# 2021-04-16_BOSS-RoboClaw-Breakout.net
KiCad netlist of a schematic drawn in EAGLE
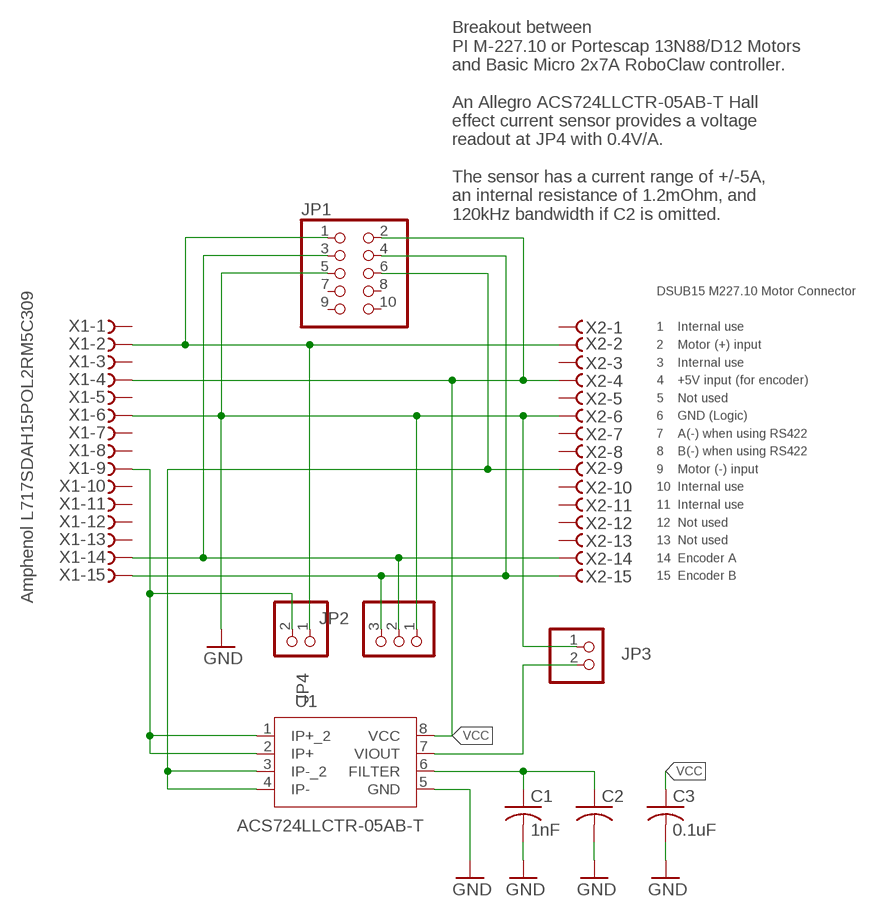
[diagram p0: schematic, sheet 1]

(export (version "E")
  (design (tool "Eeschema 10.0.6"))
  (components
    (comp (ref "C1")
      (value "1nF")
      (footprint "eagle-import:C0805")
      (libsource (lib "eagle-import") (part "C-USC0805"))
    )
    (comp (ref "C2")
      (value "C-USC0805")
      (footprint "eagle-import:C0805")
      (libsource (lib "eagle-import") (part "C-USC0805"))
    )
    (comp (ref "C3")
      (value "0.1uF")
      (footprint "eagle-import:C0805")
      (libsource (lib "eagle-import") (part "C-USC0805"))
    )
    (comp (ref "JP1")
      (value "PINHD-2X5")
      (footprint "eagle-import:2X05")
      (libsource (lib "eagle-import") (part "PINHD-2X5"))
    )
    (comp (ref "JP2")
      (value "PINHD-1X3")
      (footprint "eagle-import:1X03")
      (libsource (lib "eagle-import") (part "PINHD-1X3"))
    )
    (comp (ref "JP3")
      (value "PINHD-1X2")
      (footprint "eagle-import:1X02")
      (libsource (lib "eagle-import") (part "PINHD-1X2"))
    )
    (comp (ref "JP4")
      (value "PINHD-1X2")
      (footprint "eagle-import:1X02")
      (libsource (lib "eagle-import") (part "PINHD-1X2"))
    )
    (comp (ref "U1")
      (value "ACS724LLCTR-05AB-T")
      (footprint "eagle-import:IC8_ACS724LLCTR-05AB-T_ALM")
      (fields (field (name "COPYRIGHT") "Copyright (C) 2018 Accelerated Designs. All rights reserved"))
      (libsource (lib "eagle-import") (part "CURRENTSENSOR-ACS724LLCTR-05AB-T"))
    )
    (comp (ref "X1")
      (value "Amphenol L717SDAH15POL2RM5C309")
      (footprint "eagle-import:H2M15ST")
      (libsource (lib "eagle-import") (part "D-SUB15-H2M15ST"))
    )
    (comp (ref "X2")
      (value "Amphenol L77SDAH15SOL2RM8C309")
      (footprint "eagle-import:H2R15ST")
      (libsource (lib "eagle-import") (part "D-SUB15-H2R15ST"))
    )
  )
  (nets
    (net (code "1") (name "GND") (class "Default")
      (node (ref "C1") (pin "2") (pinfunction "2_2") (pintype "passive"))
      (node (ref "C2") (pin "2") (pinfunction "2_2") (pintype "passive"))
      (node (ref "C3") (pin "2") (pinfunction "2_2") (pintype "passive"))
      (node (ref "JP1") (pin "5") (pinfunction "5_5") (pintype "passive"))
      (node (ref "JP2") (pin "1") (pinfunction "1_1") (pintype "passive"))
      (node (ref "JP3") (pin "1") (pinfunction "1_1") (pintype "passive"))
      (node (ref "U1") (pin "5") (pinfunction "GND_5") (pintype "passive"))
      (node (ref "X1") (pin "6") (pinfunction "F_6") (pintype "passive"))
      (node (ref "X2") (pin "6") (pinfunction "F_6") (pintype "passive"))
    )
    (net (code "2") (name "Net-(U1-FILTER)") (class "Default")
      (node (ref "C1") (pin "1") (pinfunction "1_1") (pintype "passive"))
      (node (ref "C2") (pin "1") (pinfunction "1_1") (pintype "passive"))
      (node (ref "U1") (pin "6") (pinfunction "FILTER_6") (pintype "passive"))
    )
    (net (code "3") (name "Net-(U1-IP+)") (class "Default")
      (node (ref "JP4") (pin "2") (pinfunction "2_2") (pintype "passive"))
      (node (ref "U1") (pin "1") (pinfunction "IP+_2_1") (pintype "passive"))
      (node (ref "U1") (pin "2") (pinfunction "IP+_2") (pintype "passive"))
      (node (ref "X1") (pin "9") (pinfunction "F_9") (pintype "passive"))
    )
    (net (code "4") (name "Net-(U1-IP-)") (class "Default")
      (node (ref "JP1") (pin "6") (pinfunction "6_6") (pintype "passive"))
      (node (ref "U1") (pin "3") (pinfunction "IP-_2_3") (pintype "bidirectional"))
      (node (ref "U1") (pin "4") (pinfunction "IP-_4") (pintype "bidirectional"))
      (node (ref "X2") (pin "9") (pinfunction "F_9") (pintype "passive"))
    )
    (net (code "5") (name "Net-(U1-VIOUT)") (class "Default")
      (node (ref "JP3") (pin "2") (pinfunction "2_2") (pintype "passive"))
      (node (ref "U1") (pin "7") (pinfunction "VIOUT_7") (pintype "output"))
    )
    (net (code "6") (name "Net-(X1F-F)") (class "Default")
      (node (ref "JP1") (pin "3") (pinfunction "3_3") (pintype "passive"))
      (node (ref "JP2") (pin "2") (pinfunction "2_2") (pintype "passive"))
      (node (ref "X1") (pin "14") (pinfunction "F_14") (pintype "passive"))
      (node (ref "X2") (pin "14") (pinfunction "F_14") (pintype "passive"))
    )
    (net (code "7") (name "Net-(X1G-F)") (class "Default")
      (node (ref "JP1") (pin "4") (pinfunction "4_4") (pintype "passive"))
      (node (ref "JP2") (pin "3") (pinfunction "3_3") (pintype "passive"))
      (node (ref "X1") (pin "15") (pinfunction "F_15") (pintype "passive"))
      (node (ref "X2") (pin "15") (pinfunction "F_15") (pintype "passive"))
    )
    (net (code "8") (name "Net-(X1H-F)") (class "Default")
      (node (ref "JP1") (pin "1") (pinfunction "1_1") (pintype "passive"))
      (node (ref "JP4") (pin "1") (pinfunction "1_1") (pintype "passive"))
      (node (ref "X1") (pin "2") (pinfunction "F_2") (pintype "passive"))
      (node (ref "X2") (pin "2") (pinfunction "F_2") (pintype "passive"))
    )
    (net (code "9") (name "VCC") (class "Default")
      (node (ref "C3") (pin "1") (pinfunction "1_1") (pintype "passive"))
      (node (ref "JP1") (pin "2") (pinfunction "2_2") (pintype "passive"))
      (node (ref "U1") (pin "8") (pinfunction "VCC_8") (pintype "power_in"))
      (node (ref "X1") (pin "4") (pinfunction "F_4") (pintype "passive"))
      (node (ref "X2") (pin "4") (pinfunction "F_4") (pintype "passive"))
    )
    (net (code "10") (name "unconnected-(JP1-Pad7)") (class "Default")
      (node (ref "JP1") (pin "7") (pinfunction "7_7") (pintype "passive"))
    )
    (net (code "11") (name "unconnected-(JP1-Pad8)") (class "Default")
      (node (ref "JP1") (pin "8") (pinfunction "8_8") (pintype "passive"))
    )
    (net (code "12") (name "unconnected-(JP1-Pad9)") (class "Default")
      (node (ref "JP1") (pin "9") (pinfunction "9_9") (pintype "passive"))
    )
    (net (code "13") (name "unconnected-(JP1-Pad10)") (class "Default")
      (node (ref "JP1") (pin "10") (pinfunction "10_10") (pintype "passive"))
    )
    (net (code "14") (name "unconnected-(X1A-F-Pad1)") (class "Default")
      (node (ref "X1") (pin "1") (pinfunction "F_1") (pintype "passive"))
    )
    (net (code "15") (name "unconnected-(X1B-F-Pad10)") (class "Default")
      (node (ref "X1") (pin "10") (pinfunction "F_10") (pintype "passive"))
    )
    (net (code "16") (name "unconnected-(X1C-F-Pad11)") (class "Default")
      (node (ref "X1") (pin "11") (pinfunction "F_11") (pintype "passive"))
    )
    (net (code "17") (name "unconnected-(X1D-F-Pad12)") (class "Default")
      (node (ref "X1") (pin "12") (pinfunction "F_12") (pintype "passive"))
    )
    (net (code "18") (name "unconnected-(X1E-F-Pad13)") (class "Default")
      (node (ref "X1") (pin "13") (pinfunction "F_13") (pintype "passive"))
    )
    (net (code "19") (name "unconnected-(X1I-F-Pad3)") (class "Default")
      (node (ref "X1") (pin "3") (pinfunction "F_3") (pintype "passive"))
    )
    (net (code "20") (name "unconnected-(X1K-F-Pad5)") (class "Default")
      (node (ref "X1") (pin "5") (pinfunction "F_5") (pintype "passive"))
    )
    (net (code "21") (name "unconnected-(X1M-F-Pad7)") (class "Default")
      (node (ref "X1") (pin "7") (pinfunction "F_7") (pintype "passive"))
    )
    (net (code "22") (name "unconnected-(X1N-F-Pad8)") (class "Default")
      (node (ref "X1") (pin "8") (pinfunction "F_8") (pintype "passive"))
    )
    (net (code "23") (name "unconnected-(X2A-F-Pad1)") (class "Default")
      (node (ref "X2") (pin "1") (pinfunction "F_1") (pintype "passive"))
    )
    (net (code "24") (name "unconnected-(X2B-F-Pad10)") (class "Default")
      (node (ref "X2") (pin "10") (pinfunction "F_10") (pintype "passive"))
    )
    (net (code "25") (name "unconnected-(X2C-F-Pad11)") (class "Default")
      (node (ref "X2") (pin "11") (pinfunction "F_11") (pintype "passive"))
    )
    (net (code "26") (name "unconnected-(X2D-F-Pad12)") (class "Default")
      (node (ref "X2") (pin "12") (pinfunction "F_12") (pintype "passive"))
    )
    (net (code "27") (name "unconnected-(X2E-F-Pad13)") (class "Default")
      (node (ref "X2") (pin "13") (pinfunction "F_13") (pintype "passive"))
    )
    (net (code "28") (name "unconnected-(X2I-F-Pad3)") (class "Default")
      (node (ref "X2") (pin "3") (pinfunction "F_3") (pintype "passive"))
    )
    (net (code "29") (name "unconnected-(X2K-F-Pad5)") (class "Default")
      (node (ref "X2") (pin "5") (pinfunction "F_5") (pintype "passive"))
    )
    (net (code "30") (name "unconnected-(X2M-F-Pad7)") (class "Default")
      (node (ref "X2") (pin "7") (pinfunction "F_7") (pintype "passive"))
    )
    (net (code "31") (name "unconnected-(X2N-F-Pad8)") (class "Default")
      (node (ref "X2") (pin "8") (pinfunction "F_8") (pintype "passive"))
    )
  )
)
